# Pre_LM358.net
KiCad netlist of a schematic drawn in EAGLE
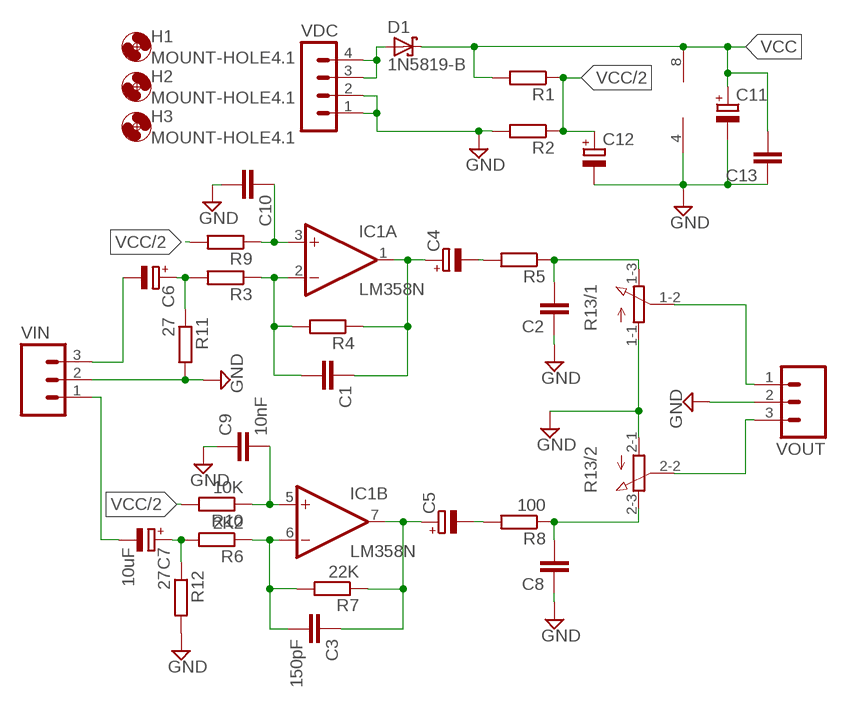
[diagram p0: schematic, sheet 1]

(export (version "E")
  (design (tool "Eeschema 10.0.6"))
  (components
    (comp (ref "C1")
      (value "C-EU025-025X050")
      (footprint "eagle-import:C025-025X050")
      (libsource (lib "eagle-import") (part "C-EU025-025X050"))
    )
    (comp (ref "C2")
      (value "C-EU025-025X050")
      (footprint "eagle-import:C025-025X050")
      (libsource (lib "eagle-import") (part "C-EU025-025X050"))
    )
    (comp (ref "C3")
      (value "150pF")
      (footprint "eagle-import:C025-025X050")
      (libsource (lib "eagle-import") (part "C-EU025-025X050"))
    )
    (comp (ref "C4")
      (value "CPOL-EUE2.5-5")
      (footprint "eagle-import:E2,5-5")
      (libsource (lib "eagle-import") (part "CPOL-EUE2.5-5"))
    )
    (comp (ref "C5")
      (value "CPOL-EUE2.5-5")
      (footprint "eagle-import:E2,5-5")
      (libsource (lib "eagle-import") (part "CPOL-EUE2.5-5"))
    )
    (comp (ref "C6")
      (value "CPOL-EUE2.5-5")
      (footprint "eagle-import:E2,5-5")
      (libsource (lib "eagle-import") (part "CPOL-EUE2.5-5"))
    )
    (comp (ref "C7")
      (value "10uF")
      (footprint "eagle-import:E2,5-5")
      (libsource (lib "eagle-import") (part "CPOL-EUE2.5-5"))
    )
    (comp (ref "C8")
      (value "C-EU025-025X050")
      (footprint "eagle-import:C025-025X050")
      (libsource (lib "eagle-import") (part "C-EU025-025X050"))
    )
    (comp (ref "C9")
      (value "10nF")
      (footprint "eagle-import:C025-025X050")
      (libsource (lib "eagle-import") (part "C-EU025-025X050"))
    )
    (comp (ref "C10")
      (value "C-EU025-025X050")
      (footprint "eagle-import:C025-025X050")
      (libsource (lib "eagle-import") (part "C-EU025-025X050"))
    )
    (comp (ref "C11")
      (value "CPOL-EUE2.5-7")
      (footprint "eagle-import:E2,5-7")
      (libsource (lib "eagle-import") (part "resistor_CPOL-EUE2.5-7"))
    )
    (comp (ref "C12")
      (value "CPOL-EUE2-4")
      (footprint "eagle-import:E2-4")
      (libsource (lib "eagle-import") (part "resistor_CPOL-EUE2-4"))
    )
    (comp (ref "C13")
      (value "C-EU025-025X050")
      (footprint "eagle-import:C025-025X050")
      (libsource (lib "eagle-import") (part "C-EU025-025X050"))
    )
    (comp (ref "D1")
      (value "1N5819-B")
      (footprint "eagle-import:DO41-7.6")
      (libsource (lib "eagle-import") (part "1N5819-B"))
    )
    (comp (ref "H1")
      (value "MOUNT-HOLE4.1")
      (footprint "eagle-import:4,1")
      (libsource (lib "eagle-import") (part "MOUNT-HOLE4.1"))
    )
    (comp (ref "H2")
      (value "MOUNT-HOLE4.1")
      (footprint "eagle-import:4,1")
      (libsource (lib "eagle-import") (part "MOUNT-HOLE4.1"))
    )
    (comp (ref "H3")
      (value "MOUNT-HOLE4.1")
      (footprint "eagle-import:4,1")
      (libsource (lib "eagle-import") (part "MOUNT-HOLE4.1"))
    )
    (comp (ref "IC1")
      (value "LM358N")
      (footprint "eagle-import:DIL08")
      (libsource (lib "eagle-import") (part "LM358N"))
    )
    (comp (ref "R1")
      (value "R-EU_0207/7")
      (footprint "eagle-import:0207_7")
      (libsource (lib "eagle-import") (part "R-EU_0207/7"))
    )
    (comp (ref "R2")
      (value "R-EU_0207/7")
      (footprint "eagle-import:0207_7")
      (libsource (lib "eagle-import") (part "R-EU_0207/7"))
    )
    (comp (ref "R3")
      (value "R-EU_0207/7")
      (footprint "eagle-import:0207_7")
      (libsource (lib "eagle-import") (part "R-EU_0207/7"))
    )
    (comp (ref "R4")
      (value "R-EU_0207/7")
      (footprint "eagle-import:0207_7")
      (libsource (lib "eagle-import") (part "R-EU_0207/7"))
    )
    (comp (ref "R5")
      (value "R-EU_0207/7")
      (footprint "eagle-import:0207_7")
      (libsource (lib "eagle-import") (part "R-EU_0207/7"))
    )
    (comp (ref "R6")
      (value "2K2")
      (footprint "eagle-import:0207_7")
      (libsource (lib "eagle-import") (part "R-EU_0207/7"))
    )
    (comp (ref "R7")
      (value "22K")
      (footprint "eagle-import:0207_7")
      (libsource (lib "eagle-import") (part "R-EU_0207/7"))
    )
    (comp (ref "R8")
      (value "100")
      (footprint "eagle-import:0207_7")
      (libsource (lib "eagle-import") (part "R-EU_0207/7"))
    )
    (comp (ref "R9")
      (value "R-EU_0207/7")
      (footprint "eagle-import:0207_7")
      (libsource (lib "eagle-import") (part "R-EU_0207/7"))
    )
    (comp (ref "R10")
      (value "10K")
      (footprint "eagle-import:0207_7")
      (libsource (lib "eagle-import") (part "R-EU_0207/7"))
    )
    (comp (ref "R11")
      (value "27")
      (footprint "eagle-import:0207_7")
      (libsource (lib "eagle-import") (part "R-EU_0207/7"))
    )
    (comp (ref "R12")
      (value "27")
      (footprint "eagle-import:0207_7")
      (libsource (lib "eagle-import") (part "R-EU_0207/7"))
    )
    (comp (ref "R13")
      (value "3RP/1610G")
      (footprint "eagle-import:3RP_1610G")
      (libsource (lib "eagle-import") (part "3RP/1610G"))
    )
    (comp (ref "VDC")
      (value "MA04-1")
      (footprint "eagle-import:MA04-1")
      (libsource (lib "eagle-import") (part "MA04-1"))
    )
    (comp (ref "VIN")
      (value "MA03")
      (footprint "eagle-import:03P")
      (libsource (lib "eagle-import") (part "MA03"))
    )
    (comp (ref "VOUT")
      (value "MA03")
      (footprint "eagle-import:03P")
      (libsource (lib "eagle-import") (part "MA03"))
    )
  )
  (nets
    (net (code "1") (name "GND") (class "Default")
      (node (ref "C10") (pin "2") (pinfunction "2_2") (pintype "passive"))
      (node (ref "C11") (pin "-") (pinfunction "-_-") (pintype "passive"))
      (node (ref "C12") (pin "-") (pinfunction "-_-") (pintype "passive"))
      (node (ref "C13") (pin "1") (pinfunction "1_1") (pintype "passive"))
      (node (ref "C2") (pin "1") (pinfunction "1_1") (pintype "passive"))
      (node (ref "C8") (pin "1") (pinfunction "1_1") (pintype "passive"))
      (node (ref "C9") (pin "1") (pinfunction "1_1") (pintype "passive"))
      (node (ref "IC1") (pin "4") (pinfunction "V-_4") (pintype "power_in"))
      (node (ref "R11") (pin "2") (pinfunction "2_2") (pintype "passive"))
      (node (ref "R12") (pin "2") (pinfunction "2_2") (pintype "passive"))
      (node (ref "R13") (pin "1-1") (pinfunction "A_1-1") (pintype "passive"))
      (node (ref "R13") (pin "2-1") (pinfunction "A_2-1") (pintype "passive"))
      (node (ref "R2") (pin "2") (pinfunction "2_2") (pintype "passive"))
      (node (ref "VDC") (pin "1") (pinfunction "1_1") (pintype "passive"))
      (node (ref "VDC") (pin "2") (pinfunction "2_2") (pintype "passive"))
      (node (ref "VIN") (pin "2") (pinfunction "2_2") (pintype "passive"))
      (node (ref "VOUT") (pin "2") (pinfunction "2_2") (pintype "passive"))
    )
    (net (code "2") (name "Net-(C4-Pad-)") (class "Default")
      (node (ref "C4") (pin "-") (pinfunction "-_-") (pintype "passive"))
      (node (ref "R5") (pin "2") (pinfunction "2_2") (pintype "passive"))
    )
    (net (code "3") (name "Net-(C5-Pad-)") (class "Default")
      (node (ref "C5") (pin "-") (pinfunction "-_-") (pintype "passive"))
      (node (ref "R8") (pin "2") (pinfunction "2_2") (pintype "passive"))
    )
    (net (code "4") (name "Net-(C6-Pad+)") (class "Default")
      (node (ref "C6") (pin "+") (pinfunction "+_+") (pintype "passive"))
      (node (ref "R11") (pin "1") (pinfunction "1_1") (pintype "passive"))
      (node (ref "R3") (pin "2") (pinfunction "2_2") (pintype "passive"))
    )
    (net (code "5") (name "Net-(C6-Pad-)") (class "Default")
      (node (ref "C6") (pin "-") (pinfunction "-_-") (pintype "passive"))
      (node (ref "VIN") (pin "3") (pinfunction "3_3") (pintype "passive"))
    )
    (net (code "6") (name "Net-(C7-Pad+)") (class "Default")
      (node (ref "C7") (pin "+") (pinfunction "+_+") (pintype "passive"))
      (node (ref "R12") (pin "1") (pinfunction "1_1") (pintype "passive"))
      (node (ref "R6") (pin "2") (pinfunction "2_2") (pintype "passive"))
    )
    (net (code "7") (name "Net-(C7-Pad-)") (class "Default")
      (node (ref "C7") (pin "-") (pinfunction "-_-") (pintype "passive"))
      (node (ref "VIN") (pin "1") (pinfunction "1_1") (pintype "passive"))
    )
    (net (code "8") (name "Net-(D1-PadA)") (class "Default")
      (node (ref "D1") (pin "A") (pinfunction "A_A") (pintype "passive"))
      (node (ref "VDC") (pin "3") (pinfunction "3_3") (pintype "passive"))
      (node (ref "VDC") (pin "4") (pinfunction "4_4") (pintype "passive"))
    )
    (net (code "9") (name "Net-(IC1A-+IN)") (class "Default")
      (node (ref "C10") (pin "1") (pinfunction "1_1") (pintype "passive"))
      (node (ref "IC1") (pin "3") (pinfunction "+IN_3") (pintype "input"))
      (node (ref "R9") (pin "1") (pinfunction "1_1") (pintype "passive"))
    )
    (net (code "10") (name "Net-(IC1A--IN)") (class "Default")
      (node (ref "C1") (pin "2") (pinfunction "2_2") (pintype "passive"))
      (node (ref "IC1") (pin "2") (pinfunction "-IN_2") (pintype "input"))
      (node (ref "R3") (pin "1") (pinfunction "1_1") (pintype "passive"))
      (node (ref "R4") (pin "2") (pinfunction "2_2") (pintype "passive"))
    )
    (net (code "11") (name "Net-(IC1A-OUT)") (class "Default")
      (node (ref "C1") (pin "1") (pinfunction "1_1") (pintype "passive"))
      (node (ref "C4") (pin "+") (pinfunction "+_+") (pintype "passive"))
      (node (ref "IC1") (pin "1") (pinfunction "OUT_1") (pintype "output"))
      (node (ref "R4") (pin "1") (pinfunction "1_1") (pintype "passive"))
    )
    (net (code "12") (name "Net-(IC1B-+IN)") (class "Default")
      (node (ref "C9") (pin "2") (pinfunction "2_2") (pintype "passive"))
      (node (ref "IC1") (pin "5") (pinfunction "+IN_5") (pintype "input"))
      (node (ref "R10") (pin "1") (pinfunction "1_1") (pintype "passive"))
    )
    (net (code "13") (name "Net-(IC1B--IN)") (class "Default")
      (node (ref "C3") (pin "2") (pinfunction "2_2") (pintype "passive"))
      (node (ref "IC1") (pin "6") (pinfunction "-IN_6") (pintype "input"))
      (node (ref "R6") (pin "1") (pinfunction "1_1") (pintype "passive"))
      (node (ref "R7") (pin "2") (pinfunction "2_2") (pintype "passive"))
    )
    (net (code "14") (name "Net-(IC1B-OUT)") (class "Default")
      (node (ref "C3") (pin "1") (pinfunction "1_1") (pintype "passive"))
      (node (ref "C5") (pin "+") (pinfunction "+_+") (pintype "passive"))
      (node (ref "IC1") (pin "7") (pinfunction "OUT_7") (pintype "output"))
      (node (ref "R7") (pin "1") (pinfunction "1_1") (pintype "passive"))
    )
    (net (code "15") (name "Net-(R13A-E)") (class "Default")
      (node (ref "C2") (pin "2") (pinfunction "2_2") (pintype "passive"))
      (node (ref "R13") (pin "1-3") (pinfunction "E_1-3") (pintype "passive"))
      (node (ref "R5") (pin "1") (pinfunction "1_1") (pintype "passive"))
    )
    (net (code "16") (name "Net-(R13A-S)") (class "Default")
      (node (ref "R13") (pin "1-2") (pinfunction "S_1-2") (pintype "passive"))
      (node (ref "VOUT") (pin "1") (pinfunction "1_1") (pintype "passive"))
    )
    (net (code "17") (name "Net-(R13B-E)") (class "Default")
      (node (ref "C8") (pin "2") (pinfunction "2_2") (pintype "passive"))
      (node (ref "R13") (pin "2-3") (pinfunction "E_2-3") (pintype "passive"))
      (node (ref "R8") (pin "1") (pinfunction "1_1") (pintype "passive"))
    )
    (net (code "18") (name "Net-(R13B-S)") (class "Default")
      (node (ref "R13") (pin "2-2") (pinfunction "S_2-2") (pintype "passive"))
      (node (ref "VOUT") (pin "3") (pinfunction "3_3") (pintype "passive"))
    )
    (net (code "19") (name "VCC") (class "Default")
      (node (ref "C11") (pin "+") (pinfunction "+_+") (pintype "passive"))
      (node (ref "C13") (pin "2") (pinfunction "2_2") (pintype "passive"))
      (node (ref "D1") (pin "C") (pinfunction "C_C") (pintype "passive"))
      (node (ref "IC1") (pin "8") (pinfunction "V+_8") (pintype "power_in"))
      (node (ref "R1") (pin "2") (pinfunction "2_2") (pintype "passive"))
    )
    (net (code "20") (name "VCC{slash}2") (class "Default")
      (node (ref "C12") (pin "+") (pinfunction "+_+") (pintype "passive"))
      (node (ref "R1") (pin "1") (pinfunction "1_1") (pintype "passive"))
      (node (ref "R10") (pin "2") (pinfunction "2_2") (pintype "passive"))
      (node (ref "R2") (pin "1") (pinfunction "1_1") (pintype "passive"))
      (node (ref "R9") (pin "2") (pinfunction "2_2") (pintype "passive"))
    )
  )
)
